# MikroBus.net
KiCad netlist of a schematic drawn in Altium Designer
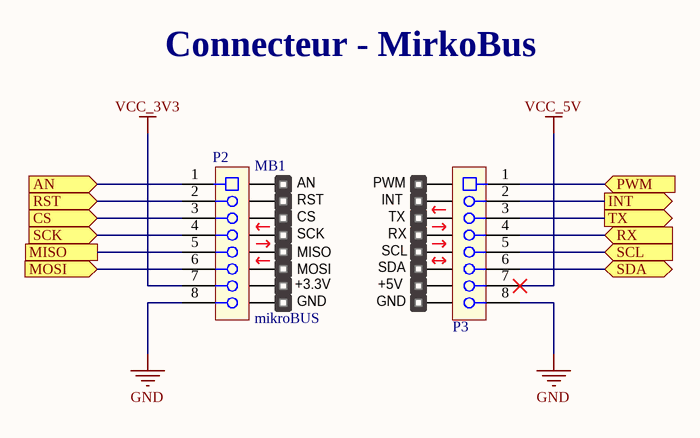
[diagram p0: MikroBus.SchDoc]

(export (version "E")
  (design (tool "Eeschema 10.0.6"))
  (components
    (comp (ref "MB1")
      (value "mikroBUS")
      (footprint "mikroBUS-Large-No-Connector")
      (description "mikroBUS compatible add-on board")
      (libsource (lib "TEP-AltiumLib-Modules") (part "mikroBUS compatible add-on board"))
    )
    (comp (ref "P2")
      (value "ESQ-108-14-T-S")
      (footprint "CONN_SKT_01X08_100MIL-ELEVATED-LONGPIN")
      (description "CONN SOCKET 8pos 100mils Elevated")
      (libsource (lib "TEP-AltiumLib-Connectors") (part "CONN-100MIL-SKT-01X08_ELEVATED_LONGPIN"))
    )
    (comp (ref "P3")
      (value "ESQ-108-14-T-S")
      (footprint "CONN_SKT_01X08_100MIL-ELEVATED-LONGPIN")
      (description "CONN SOCKET 8pos 100mils Elevated")
      (libsource (lib "") (part "CONN-100MIL-SKT-01X08_ELEVATED_LONGPIN_1"))
    )
  )
  (nets
    (net (code "1") (name "/AN") (class "Default")
      (node (ref "P2") (pin "1") (pinfunction "1_1") (pintype "passive"))
    )
    (net (code "2") (name "/CS") (class "Default")
      (node (ref "P2") (pin "3") (pinfunction "3_3") (pintype "passive"))
    )
    (net (code "3") (name "/INT") (class "Default")
      (node (ref "P3") (pin "2") (pinfunction "2_2") (pintype "passive"))
    )
    (net (code "4") (name "/MISO") (class "Default")
      (node (ref "P2") (pin "5") (pinfunction "5_5") (pintype "passive"))
    )
    (net (code "5") (name "/MOSI") (class "Default")
      (node (ref "P2") (pin "6") (pinfunction "6_6") (pintype "passive"))
    )
    (net (code "6") (name "/PWM") (class "Default")
      (node (ref "P3") (pin "1") (pinfunction "1_1") (pintype "passive"))
    )
    (net (code "7") (name "/RST") (class "Default")
      (node (ref "P2") (pin "2") (pinfunction "2_2") (pintype "passive"))
    )
    (net (code "8") (name "/RX") (class "Default")
      (node (ref "P3") (pin "4") (pinfunction "4_4") (pintype "passive"))
    )
    (net (code "9") (name "/SCK") (class "Default")
      (node (ref "P2") (pin "4") (pinfunction "4_4") (pintype "passive"))
    )
    (net (code "10") (name "/SCL") (class "Default")
      (node (ref "P3") (pin "5") (pinfunction "5_5") (pintype "passive"))
    )
    (net (code "11") (name "/SDA") (class "Default")
      (node (ref "P3") (pin "6") (pinfunction "6_6") (pintype "passive"))
    )
    (net (code "12") (name "/TX") (class "Default")
      (node (ref "P3") (pin "3") (pinfunction "3_3") (pintype "passive"))
    )
    (net (code "13") (name "GND") (class "Default")
      (node (ref "P2") (pin "8") (pinfunction "8_8") (pintype "passive"))
      (node (ref "P3") (pin "8") (pinfunction "8_8") (pintype "passive"))
    )
    (net (code "14") (name "VCC_3V3") (class "Default")
      (node (ref "P2") (pin "7") (pinfunction "7_7") (pintype "passive"))
    )
    (net (code "15") (name "VCC_5V") (class "Default")
      (node (ref "P3") (pin "7") (pinfunction "7_7") (pintype "passive"))
    )
    (net (code "16") (name "unconnected-(MB1-3.3V-Pad7)") (class "Default")
      (node (ref "MB1") (pin "7") (pinfunction "3.3V_7") (pintype "passive"))
    )
    (net (code "17") (name "unconnected-(MB1-5V-Pad10)") (class "Default")
      (node (ref "MB1") (pin "10") (pinfunction "5V_10") (pintype "passive"))
    )
    (net (code "18") (name "unconnected-(MB1-AN-Pad1)") (class "Default")
      (node (ref "MB1") (pin "1") (pinfunction "AN_1") (pintype "passive"))
    )
    (net (code "19") (name "unconnected-(MB1-CS-Pad3)") (class "Default")
      (node (ref "MB1") (pin "3") (pinfunction "CS_3") (pintype "passive"))
    )
    (net (code "20") (name "unconnected-(MB1-GND-Pad8)") (class "Default")
      (node (ref "MB1") (pin "8") (pinfunction "GND_8") (pintype "passive"))
    )
    (net (code "21") (name "unconnected-(MB1-GND-Pad9)") (class "Default")
      (node (ref "MB1") (pin "9") (pinfunction "GND_9") (pintype "passive"))
    )
    (net (code "22") (name "unconnected-(MB1-INT-Pad15)") (class "Default")
      (node (ref "MB1") (pin "15") (pinfunction "INT_15") (pintype "passive"))
    )
    (net (code "23") (name "unconnected-(MB1-MISO-Pad5)") (class "Default")
      (node (ref "MB1") (pin "5") (pinfunction "MISO_5") (pintype "passive"))
    )
    (net (code "24") (name "unconnected-(MB1-MOSI-Pad6)") (class "Default")
      (node (ref "MB1") (pin "6") (pinfunction "MOSI_6") (pintype "passive"))
    )
    (net (code "25") (name "unconnected-(MB1-PWM-Pad16)") (class "Default")
      (node (ref "MB1") (pin "16") (pinfunction "PWM_16") (pintype "passive"))
    )
    (net (code "26") (name "unconnected-(MB1-RST-Pad2)") (class "Default")
      (node (ref "MB1") (pin "2") (pinfunction "RST_2") (pintype "passive"))
    )
    (net (code "27") (name "unconnected-(MB1-RX-Pad14)") (class "Default")
      (node (ref "MB1") (pin "14") (pinfunction "RX_14") (pintype "passive"))
    )
    (net (code "28") (name "unconnected-(MB1-SCK-Pad4)") (class "Default")
      (node (ref "MB1") (pin "4") (pinfunction "SCK_4") (pintype "passive"))
    )
    (net (code "29") (name "unconnected-(MB1-SCL-Pad12)") (class "Default")
      (node (ref "MB1") (pin "12") (pinfunction "SCL_12") (pintype "passive"))
    )
    (net (code "30") (name "unconnected-(MB1-SDA-Pad11)") (class "Default")
      (node (ref "MB1") (pin "11") (pinfunction "SDA_11") (pintype "passive"))
    )
    (net (code "31") (name "unconnected-(MB1-TX-Pad13)") (class "Default")
      (node (ref "MB1") (pin "13") (pinfunction "TX_13") (pintype "passive"))
    )
  )
)
